# DC-step-down.net
KiCad netlist of a schematic drawn in Altium Designer
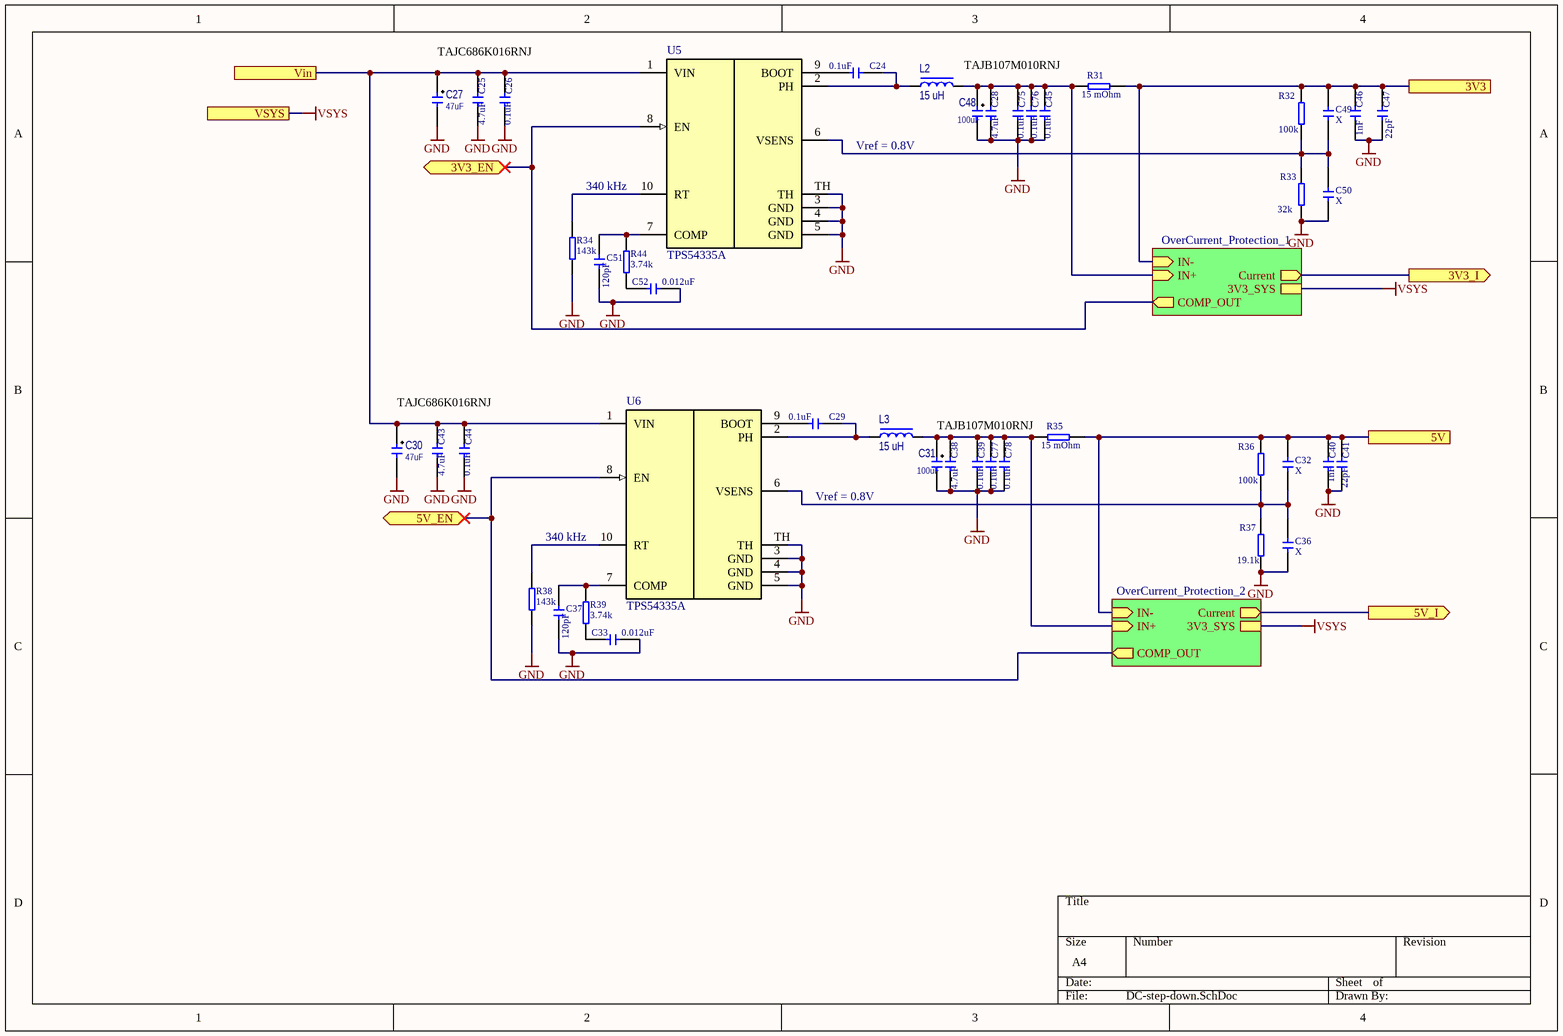
[diagram p0: DC-step-down.SchDoc]

(export (version "E")
  (design (tool "Eeschema 10.0.6"))
  (components
    (comp (ref "C24")
      (value "0.1uF")
      (footprint "CERCAP 0402")
      (description "Capacitor")
      (fields (field (name "VOLTAGE") "50V") (field (name "Comment") "CERCAP 0402 0.1uF 50V X7R"))
      (libsource (lib "!main") (part "!Capacitor"))
    )
    (comp (ref "C25")
      (value "4.7uF")
      (footprint "CERCAP 0603")
      (description "Capacitor")
      (fields (field (name "VOLTAGE") "16V") (field (name "Comment") "CERCAP 0603 4.7uF 16V X7R"))
      (libsource (lib "!main") (part "!Capacitor"))
    )
    (comp (ref "C26")
      (value "0.1uF")
      (footprint "CERCAP 0402")
      (description "Capacitor")
      (fields (field (name "VOLTAGE") "50V") (field (name "Comment") "CERCAP 0402 0.1uF 50V X7R"))
      (libsource (lib "!main") (part "!Capacitor"))
    )
    (comp (ref "C27")
      (value "47uF")
      (footprint "TECAP B")
      (description "Capacitor Polar")
      (fields (field (name "Comment") "TAJC686K016RNJ"))
      (libsource (lib "!main") (part "CapacitorP"))
    )
    (comp (ref "C28")
      (value "4.7uF")
      (footprint "CERCAP 0603")
      (description "Capacitor")
      (fields (field (name "VOLTAGE") "10V") (field (name "Comment") "CERCAP 0603 4.7uF 10V X7R"))
      (libsource (lib "!main") (part "!Capacitor"))
    )
    (comp (ref "C29")
      (value "0.1uF")
      (footprint "CERCAP 0402")
      (description "Capacitor")
      (fields (field (name "VOLTAGE") "50V") (field (name "Comment") "CERCAP 0402 0.1uF 50V X7R"))
      (libsource (lib "!main") (part "!Capacitor"))
    )
    (comp (ref "C30")
      (value "47uF")
      (footprint "TECAP B")
      (description "Capacitor Polar")
      (fields (field (name "Comment") "TAJC686K016RNJ"))
      (libsource (lib "!main") (part "CapacitorP"))
    )
    (comp (ref "C31")
      (value "100uF")
      (footprint "TECAP B")
      (description "Capacitor Polar")
      (fields (field (name "Comment") "TAJB107M010RNJ"))
      (libsource (lib "!main") (part "CapacitorP"))
    )
    (comp (ref "C32")
      (value "X")
      (footprint "CERCAP 0402")
      (description "Capacitor")
      (fields (field (name "VOLTAGE") "50V") (field (name "Comment") "CERCAP 0402 X 50V X7R"))
      (libsource (lib "!main") (part "!Capacitor"))
    )
    (comp (ref "C33")
      (value "0.012uF")
      (footprint "CERCAP 0402")
      (description "Capacitor")
      (fields (field (name "VOLTAGE") "50V") (field (name "Comment") "CERCAP 0402 0.012uF 50V X7R"))
      (libsource (lib "!main") (part "!Capacitor"))
    )
    (comp (ref "C36")
      (value "X")
      (footprint "CERCAP 0402")
      (description "Capacitor")
      (fields (field (name "VOLTAGE") "50V") (field (name "Comment") "CERCAP 0402 X 50V X7R"))
      (libsource (lib "!main") (part "!Capacitor"))
    )
    (comp (ref "C37")
      (value "120pF")
      (footprint "CERCAP 0402")
      (description "Capacitor")
      (fields (field (name "VOLTAGE") "50V") (field (name "Comment") "CERCAP 0402 120pF 50V X7R"))
      (libsource (lib "!main") (part "!Capacitor"))
    )
    (comp (ref "C38")
      (value "4.7uF")
      (footprint "CERCAP 0603")
      (description "Capacitor")
      (fields (field (name "VOLTAGE") "10V") (field (name "Comment") "CERCAP 0603 4.7uF 10V X7R"))
      (libsource (lib "!main") (part "!Capacitor"))
    )
    (comp (ref "C39")
      (value "0.1uF")
      (footprint "CERCAP 0402")
      (description "Capacitor")
      (fields (field (name "VOLTAGE") "50V") (field (name "Comment") "CERCAP 0402 0.1uF 50V X7R"))
      (libsource (lib "!main") (part "!Capacitor"))
    )
    (comp (ref "C40")
      (value "1nF")
      (footprint "CERCAP 0402")
      (description "Capacitor")
      (fields (field (name "VOLTAGE") "50V") (field (name "Comment") "CERCAP 0402 1nF 50V X7R"))
      (libsource (lib "!main") (part "!Capacitor"))
    )
    (comp (ref "C41")
      (value "22pF")
      (footprint "CERCAP 0402")
      (description "Capacitor")
      (fields (field (name "VOLTAGE") "50V") (field (name "Comment") "CERCAP 0402 22pF 50V X7R"))
      (libsource (lib "!main") (part "!Capacitor"))
    )
    (comp (ref "C43")
      (value "4.7uF")
      (footprint "CERCAP 0603")
      (description "Capacitor")
      (fields (field (name "VOLTAGE") "16V") (field (name "Comment") "CERCAP 0603 4.7uF 16V X7R"))
      (libsource (lib "!main") (part "!Capacitor"))
    )
    (comp (ref "C44")
      (value "0.1uF")
      (footprint "CERCAP 0402")
      (description "Capacitor")
      (fields (field (name "VOLTAGE") "50V") (field (name "Comment") "CERCAP 0402 0.1uF 50V X7R"))
      (libsource (lib "!main") (part "!Capacitor"))
    )
    (comp (ref "C45")
      (value "0.1uF")
      (footprint "CERCAP 0402")
      (description "Capacitor")
      (fields (field (name "VOLTAGE") "50V") (field (name "Comment") "CERCAP 0402 0.1uF 50V X7R"))
      (libsource (lib "!main") (part "!Capacitor"))
    )
    (comp (ref "C46")
      (value "1nF")
      (footprint "CERCAP 0402")
      (description "Capacitor")
      (fields (field (name "VOLTAGE") "50V") (field (name "Comment") "CERCAP 0402 1nF 50V X7R"))
      (libsource (lib "!main") (part "!Capacitor"))
    )
    (comp (ref "C47")
      (value "22pF")
      (footprint "CERCAP 0402")
      (description "Capacitor")
      (fields (field (name "VOLTAGE") "50V") (field (name "Comment") "CERCAP 0402 22pF 50V X7R"))
      (libsource (lib "!main") (part "!Capacitor"))
    )
    (comp (ref "C48")
      (value "100uF")
      (footprint "TECAP B")
      (description "Capacitor Polar")
      (fields (field (name "Comment") "TAJB107M010RNJ"))
      (libsource (lib "!main") (part "CapacitorP"))
    )
    (comp (ref "C49")
      (value "X")
      (footprint "CERCAP 0402")
      (description "Capacitor")
      (fields (field (name "VOLTAGE") "50V") (field (name "Comment") "CERCAP 0402 X 50V X7R"))
      (libsource (lib "!main") (part "!Capacitor"))
    )
    (comp (ref "C50")
      (value "X")
      (footprint "CERCAP 0402")
      (description "Capacitor")
      (fields (field (name "VOLTAGE") "50V") (field (name "Comment") "CERCAP 0402 X 50V X7R"))
      (libsource (lib "!main") (part "!Capacitor"))
    )
    (comp (ref "C51")
      (value "120pF")
      (footprint "CERCAP 0402")
      (description "Capacitor")
      (fields (field (name "VOLTAGE") "50V") (field (name "Comment") "CERCAP 0402 120pF 50V X7R"))
      (libsource (lib "!main") (part "!Capacitor"))
    )
    (comp (ref "C52")
      (value "0.012uF")
      (footprint "CERCAP 0402")
      (description "Capacitor")
      (fields (field (name "VOLTAGE") "50V") (field (name "Comment") "CERCAP 0402 0.012uF 50V X7R"))
      (libsource (lib "!main") (part "!Capacitor"))
    )
    (comp (ref "C75")
      (value "0.1uF")
      (footprint "CERCAP 0402")
      (description "Capacitor")
      (fields (field (name "VOLTAGE") "50V") (field (name "Comment") "CERCAP 0402 0.1uF 50V X7R"))
      (libsource (lib "!main") (part "!Capacitor"))
    )
    (comp (ref "C76")
      (value "0.1uF")
      (footprint "CERCAP 0402")
      (description "Capacitor")
      (fields (field (name "VOLTAGE") "50V") (field (name "Comment") "CERCAP 0402 0.1uF 50V X7R"))
      (libsource (lib "!main") (part "!Capacitor"))
    )
    (comp (ref "C77")
      (value "0.1uF")
      (footprint "CERCAP 0402")
      (description "Capacitor")
      (fields (field (name "VOLTAGE") "50V") (field (name "Comment") "CERCAP 0402 0.1uF 50V X7R"))
      (libsource (lib "!main") (part "!Capacitor"))
    )
    (comp (ref "C78")
      (value "0.1uF")
      (footprint "CERCAP 0402")
      (description "Capacitor")
      (fields (field (name "VOLTAGE") "50V") (field (name "Comment") "CERCAP 0402 0.1uF 50V X7R"))
      (libsource (lib "!main") (part "!Capacitor"))
    )
    (comp (ref "L2")
      (value "15 uH")
      (footprint "IND-5x5")
      (description "Inductor")
      (fields (field (name "Comment") "IND-5x5 15 uH"))
      (libsource (lib "!main") (part "Inductor"))
    )
    (comp (ref "L3")
      (value "15 uH")
      (footprint "IND-5x5")
      (description "Inductor")
      (fields (field (name "Comment") "IND-5x5 15 uH"))
      (libsource (lib "!main") (part "Inductor"))
    )
    (comp (ref "R31")
      (value "15 mOhm")
      (footprint "RES 1210")
      (description "Resistor")
      (fields (field (name "Comment") "RES 1210 15 mOhm"))
      (libsource (lib "!main") (part "!Resistor"))
    )
    (comp (ref "R32")
      (value "100k")
      (footprint "RES 0402")
      (description "Resistor")
      (fields (field (name "Comment") "RES 0402 100k"))
      (libsource (lib "!main") (part "!Resistor"))
    )
    (comp (ref "R33")
      (value "32k")
      (footprint "RES 0402")
      (description "Resistor")
      (fields (field (name "Comment") "RES 0402 32k"))
      (libsource (lib "!main") (part "!Resistor"))
    )
    (comp (ref "R34")
      (value "143k")
      (footprint "RES 0402")
      (description "Resistor")
      (fields (field (name "Comment") "RES 0402 143k"))
      (libsource (lib "!main") (part "!Resistor"))
    )
    (comp (ref "R35")
      (value "15 mOhm")
      (footprint "RES 1210")
      (description "Resistor")
      (fields (field (name "Comment") "RES 1210 15 mOhm"))
      (libsource (lib "!main") (part "!Resistor"))
    )
    (comp (ref "R36")
      (value "100k")
      (footprint "RES 0402")
      (description "Resistor")
      (fields (field (name "Comment") "RES 0402 100k"))
      (libsource (lib "!main") (part "!Resistor"))
    )
    (comp (ref "R37")
      (value "19.1k")
      (footprint "RES 0402")
      (description "Resistor")
      (fields (field (name "Comment") "RES 0402 19.1k"))
      (libsource (lib "!main") (part "!Resistor"))
    )
    (comp (ref "R38")
      (value "143k")
      (footprint "RES 0402")
      (description "Resistor")
      (fields (field (name "Comment") "RES 0402 143k"))
      (libsource (lib "!main") (part "!Resistor"))
    )
    (comp (ref "R39")
      (value "3.74k")
      (footprint "RES 0402")
      (description "Resistor")
      (fields (field (name "Comment") "RES 0402 3.74k"))
      (libsource (lib "!main") (part "!Resistor"))
    )
    (comp (ref "R44")
      (value "3.74k")
      (footprint "RES 0402")
      (description "Resistor")
      (fields (field (name "Comment") "RES 0402 3.74k"))
      (libsource (lib "!main") (part "!Resistor"))
    )
    (comp (ref "U5")
      (value "TPS54335A")
      (footprint "VSON-10")
      (description "buck sync wEN woPG")
      (libsource (lib "dc-dc") (part "TPS54335A"))
    )
    (comp (ref "U6")
      (value "TPS54335A")
      (footprint "VSON-10")
      (description "buck sync wEN woPG")
      (libsource (lib "dc-dc") (part "TPS54335A"))
    )
  )
  (nets
    (net (code "1") (name "/3V3") (class "Default")
      (node (ref "C46") (pin "2") (pintype "passive"))
      (node (ref "C47") (pin "2") (pintype "passive"))
      (node (ref "C49") (pin "2") (pintype "passive"))
      (node (ref "R31") (pin "2") (pinfunction "12_2") (pintype "passive"))
      (node (ref "R32") (pin "2") (pinfunction "12_2") (pintype "passive"))
    )
    (net (code "2") (name "/3V3_EN") (class "Default")
      (node (ref "U5") (pin "8") (pinfunction "EN_8") (pintype "input+no_connect"))
    )
    (net (code "4") (name "/5V") (class "Default")
      (node (ref "C32") (pin "2") (pintype "passive"))
      (node (ref "C40") (pin "2") (pintype "passive"))
      (node (ref "C41") (pin "2") (pintype "passive"))
      (node (ref "R35") (pin "2") (pinfunction "12_2") (pintype "passive"))
      (node (ref "R36") (pin "2") (pinfunction "12_2") (pintype "passive"))
    )
    (net (code "5") (name "/5V_EN") (class "Default")
      (node (ref "U6") (pin "8") (pinfunction "EN_8") (pintype "input+no_connect"))
    )
    (net (code "7") (name "/IN+") (class "Default")
      (node (ref "C28") (pin "2") (pintype "passive"))
      (node (ref "C45") (pin "2") (pintype "passive"))
      (node (ref "C48") (pin "1") (pinfunction "+_1") (pintype "passive"))
      (node (ref "C75") (pin "2") (pintype "passive"))
      (node (ref "C76") (pin "2") (pintype "passive"))
      (node (ref "L2") (pin "2") (pinfunction "8_2") (pintype "passive"))
      (node (ref "R31") (pin "1") (pinfunction "11_1") (pintype "passive"))
    )
    (net (code "8") (name "/IN+_1") (class "Default")
      (node (ref "C31") (pin "1") (pinfunction "+_1") (pintype "passive"))
      (node (ref "C38") (pin "2") (pintype "passive"))
      (node (ref "C39") (pin "2") (pintype "passive"))
      (node (ref "C77") (pin "2") (pintype "passive"))
      (node (ref "C78") (pin "2") (pintype "passive"))
      (node (ref "L3") (pin "2") (pinfunction "8_2") (pintype "passive"))
      (node (ref "R35") (pin "1") (pinfunction "11_1") (pintype "passive"))
    )
    (net (code "9") (name "/Vin") (class "Default")
      (node (ref "C25") (pin "2") (pintype "passive"))
      (node (ref "C26") (pin "2") (pintype "passive"))
      (node (ref "C27") (pin "1") (pinfunction "+_1") (pintype "passive"))
      (node (ref "C30") (pin "1") (pinfunction "+_1") (pintype "passive"))
      (node (ref "C43") (pin "2") (pintype "passive"))
      (node (ref "C44") (pin "2") (pintype "passive"))
      (node (ref "U5") (pin "1") (pinfunction "VIN_1") (pintype "power_in"))
      (node (ref "U6") (pin "1") (pinfunction "VIN_1") (pintype "power_in"))
    )
    (net (code "10") (name "GND") (class "Default")
      (node (ref "C25") (pin "1") (pintype "passive"))
      (node (ref "C26") (pin "1") (pintype "passive"))
      (node (ref "C27") (pin "2") (pinfunction "-_2") (pintype "passive"))
      (node (ref "C28") (pin "1") (pintype "passive"))
      (node (ref "C30") (pin "2") (pinfunction "-_2") (pintype "passive"))
      (node (ref "C31") (pin "2") (pinfunction "-_2") (pintype "passive"))
      (node (ref "C33") (pin "1") (pintype "passive"))
      (node (ref "C36") (pin "1") (pintype "passive"))
      (node (ref "C37") (pin "2") (pintype "passive"))
      (node (ref "C38") (pin "1") (pintype "passive"))
      (node (ref "C39") (pin "1") (pintype "passive"))
      (node (ref "C40") (pin "1") (pintype "passive"))
      (node (ref "C41") (pin "1") (pintype "passive"))
      (node (ref "C43") (pin "1") (pintype "passive"))
      (node (ref "C44") (pin "1") (pintype "passive"))
      (node (ref "C45") (pin "1") (pintype "passive"))
      (node (ref "C46") (pin "1") (pintype "passive"))
      (node (ref "C47") (pin "1") (pintype "passive"))
      (node (ref "C48") (pin "2") (pinfunction "-_2") (pintype "passive"))
      (node (ref "C50") (pin "1") (pintype "passive"))
      (node (ref "C51") (pin "2") (pintype "passive"))
      (node (ref "C52") (pin "1") (pintype "passive"))
      (node (ref "C75") (pin "1") (pintype "passive"))
      (node (ref "C76") (pin "1") (pintype "passive"))
      (node (ref "C77") (pin "1") (pintype "passive"))
      (node (ref "C78") (pin "1") (pintype "passive"))
      (node (ref "R33") (pin "1") (pinfunction "11_1") (pintype "passive"))
      (node (ref "R34") (pin "1") (pinfunction "11_1") (pintype "passive"))
      (node (ref "R37") (pin "1") (pinfunction "11_1") (pintype "passive"))
      (node (ref "R38") (pin "1") (pinfunction "11_1") (pintype "passive"))
      (node (ref "U5") (pin "3") (pinfunction "GND_3") (pintype "power_in"))
      (node (ref "U5") (pin "4") (pinfunction "GND_4") (pintype "power_in"))
      (node (ref "U5") (pin "5") (pinfunction "GND_5") (pintype "power_in"))
      (node (ref "U5") (pin "TH") (pinfunction "TH_TH") (pintype "power_in"))
      (node (ref "U6") (pin "3") (pinfunction "GND_3") (pintype "power_in"))
      (node (ref "U6") (pin "4") (pinfunction "GND_4") (pintype "power_in"))
      (node (ref "U6") (pin "5") (pinfunction "GND_5") (pintype "power_in"))
      (node (ref "U6") (pin "TH") (pinfunction "TH_TH") (pintype "power_in"))
    )
    (net (code "11") (name "Net-(L2-7)") (class "Default")
      (node (ref "C24") (pin "2") (pintype "passive"))
      (node (ref "L2") (pin "1") (pinfunction "7_1") (pintype "passive"))
      (node (ref "U5") (pin "2") (pinfunction "PH_2") (pintype "power_in"))
    )
    (net (code "12") (name "Net-(L3-7)") (class "Default")
      (node (ref "C29") (pin "2") (pintype "passive"))
      (node (ref "L3") (pin "1") (pinfunction "7_1") (pintype "passive"))
      (node (ref "U6") (pin "2") (pinfunction "PH_2") (pintype "power_in"))
    )
    (net (code "13") (name "Net-(R32-11)") (class "Default")
      (node (ref "C49") (pin "1") (pintype "passive"))
      (node (ref "C50") (pin "2") (pintype "passive"))
      (node (ref "R32") (pin "1") (pinfunction "11_1") (pintype "passive"))
      (node (ref "R33") (pin "2") (pinfunction "12_2") (pintype "passive"))
      (node (ref "U5") (pin "6") (pinfunction "VSENS_6") (pintype "power_in"))
    )
    (net (code "14") (name "Net-(R34-12)") (class "Default")
      (node (ref "R34") (pin "2") (pinfunction "12_2") (pintype "passive"))
      (node (ref "U5") (pin "10") (pinfunction "RT_10") (pintype "power_in"))
    )
    (net (code "15") (name "Net-(R36-11)") (class "Default")
      (node (ref "C32") (pin "1") (pintype "passive"))
      (node (ref "C36") (pin "2") (pintype "passive"))
      (node (ref "R36") (pin "1") (pinfunction "11_1") (pintype "passive"))
      (node (ref "R37") (pin "2") (pinfunction "12_2") (pintype "passive"))
      (node (ref "U6") (pin "6") (pinfunction "VSENS_6") (pintype "power_in"))
    )
    (net (code "16") (name "Net-(R38-12)") (class "Default")
      (node (ref "R38") (pin "2") (pinfunction "12_2") (pintype "passive"))
      (node (ref "U6") (pin "10") (pinfunction "RT_10") (pintype "power_in"))
    )
    (net (code "17") (name "Net-(R39-11)") (class "Default")
      (node (ref "C33") (pin "2") (pintype "passive"))
      (node (ref "R39") (pin "1") (pinfunction "11_1") (pintype "passive"))
    )
    (net (code "18") (name "Net-(R39-12)") (class "Default")
      (node (ref "C37") (pin "1") (pintype "passive"))
      (node (ref "R39") (pin "2") (pinfunction "12_2") (pintype "passive"))
      (node (ref "U6") (pin "7") (pinfunction "COMP_7") (pintype "power_in"))
    )
    (net (code "19") (name "Net-(R44-11)") (class "Default")
      (node (ref "C52") (pin "2") (pintype "passive"))
      (node (ref "R44") (pin "1") (pinfunction "11_1") (pintype "passive"))
    )
    (net (code "20") (name "Net-(R44-12)") (class "Default")
      (node (ref "C51") (pin "1") (pintype "passive"))
      (node (ref "R44") (pin "2") (pinfunction "12_2") (pintype "passive"))
      (node (ref "U5") (pin "7") (pinfunction "COMP_7") (pintype "power_in"))
    )
    (net (code "21") (name "Net-(U5-BOOT)") (class "Default")
      (node (ref "C24") (pin "1") (pintype "passive"))
      (node (ref "U5") (pin "9") (pinfunction "BOOT_9") (pintype "power_in"))
    )
    (net (code "22") (name "Net-(U6-BOOT)") (class "Default")
      (node (ref "C29") (pin "1") (pintype "passive"))
      (node (ref "U6") (pin "9") (pinfunction "BOOT_9") (pintype "power_in"))
    )
  )
)
